# clock13.net
KiCad netlist of a schematic drawn in EAGLE
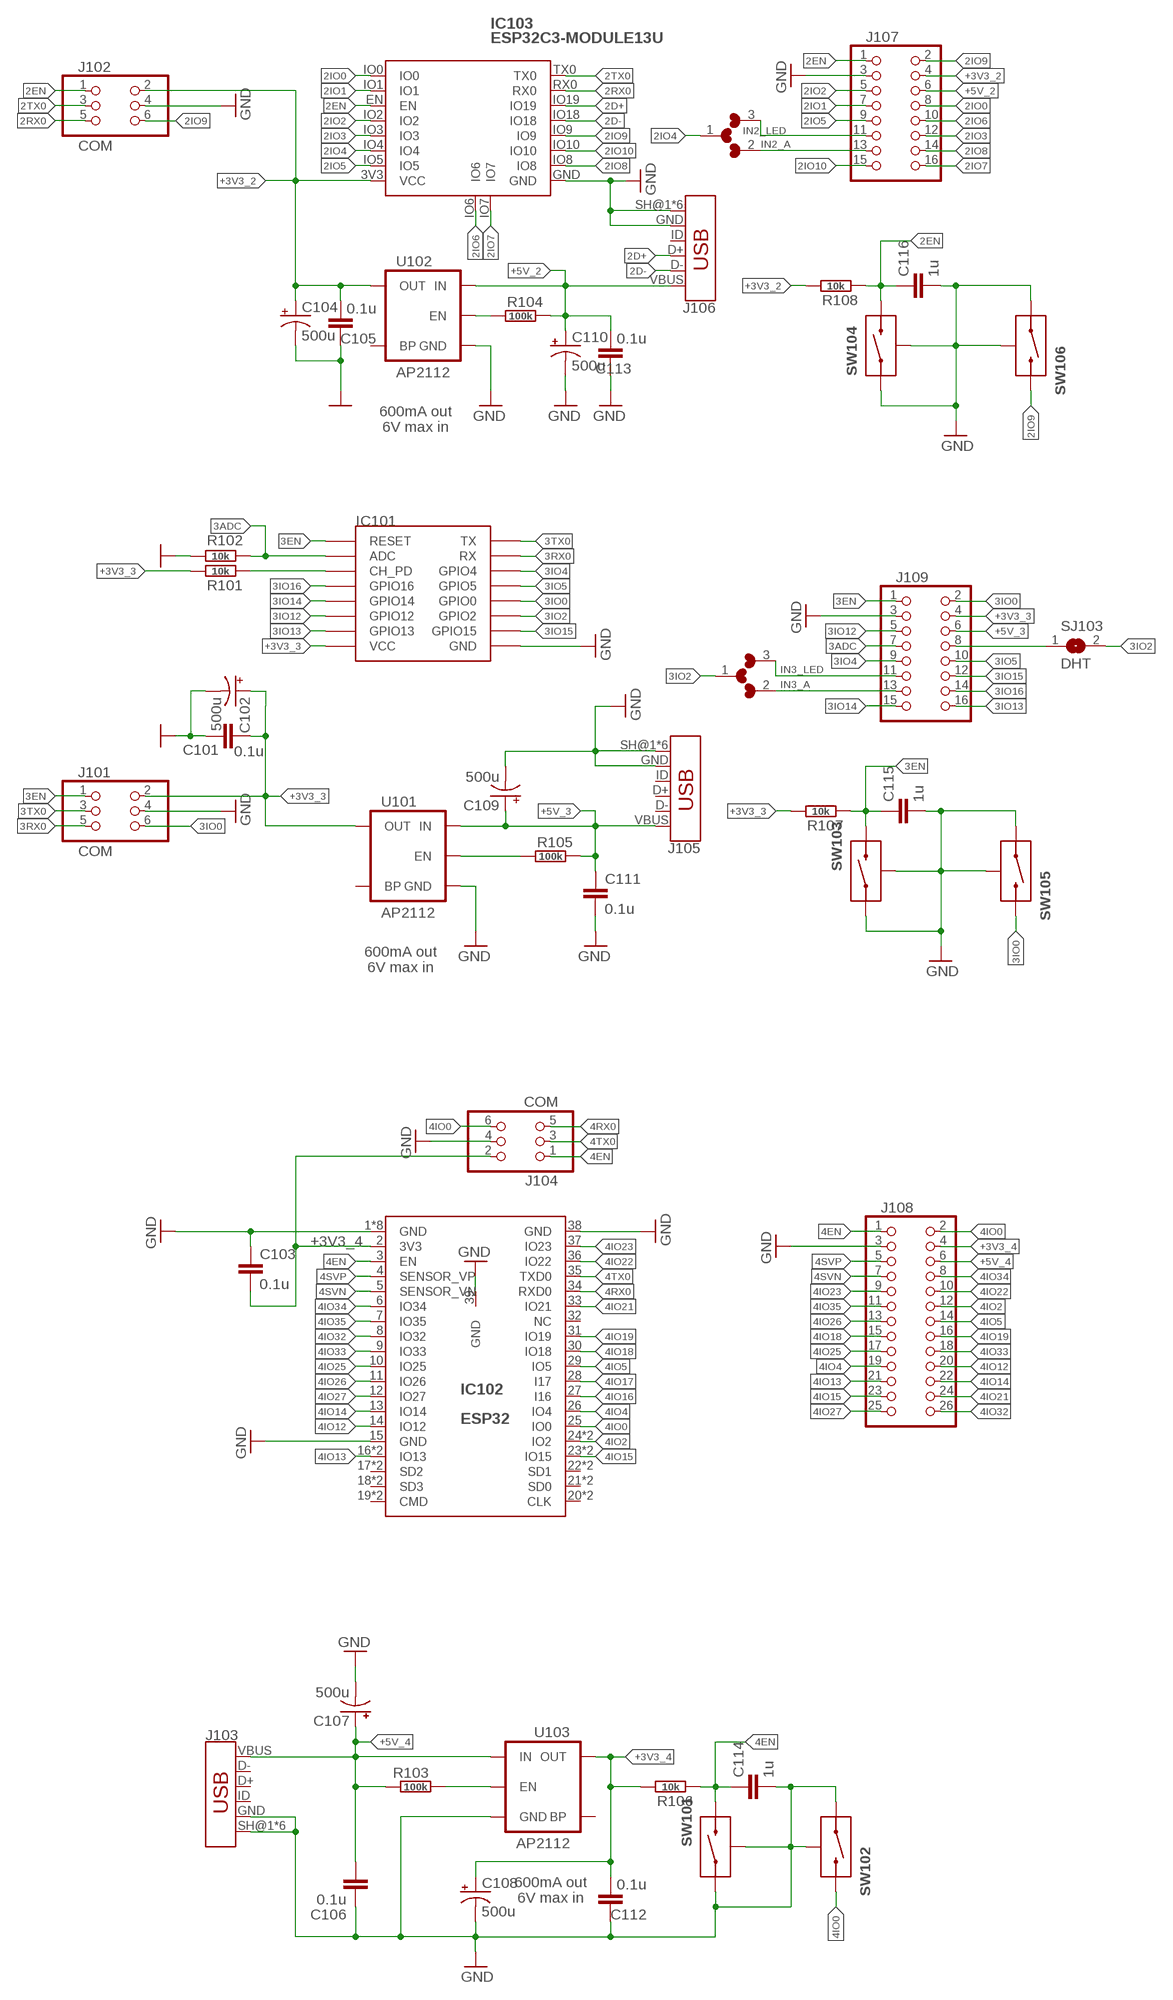
[diagram p0: schematic, sheet 1]

(export (version "E")
  (design (tool "Eeschema 10.0.6"))
  (components
    (comp (ref "C101")
      (value "0.1u")
      (footprint "eagle-import:0603-CAP")
      (libsource (lib "eagle-import") (part "CAP0603-CAP"))
    )
    (comp (ref "C102")
      (value "500u")
      (footprint "eagle-import:CPOL-RADIAL-100UF-25V")
      (libsource (lib "eagle-import") (part "CAP_POLPTH1"))
    )
    (comp (ref "C103")
      (value "0.1u")
      (footprint "eagle-import:0603-CAP")
      (libsource (lib "eagle-import") (part "CAP0603-CAP"))
    )
    (comp (ref "C104")
      (value "500u")
      (footprint "eagle-import:CPOL-RADIAL-100UF-25V")
      (libsource (lib "eagle-import") (part "CAP_POLPTH1"))
    )
    (comp (ref "C105")
      (value "0.1u")
      (footprint "eagle-import:0603-CAP")
      (libsource (lib "eagle-import") (part "CAP0603-CAP"))
    )
    (comp (ref "C106")
      (value "0.1u")
      (footprint "eagle-import:0603-CAP")
      (libsource (lib "eagle-import") (part "CAP0603-CAP"))
    )
    (comp (ref "C107")
      (value "500u")
      (footprint "eagle-import:CPOL-RADIAL-100UF-25V")
      (libsource (lib "eagle-import") (part "CAP_POLPTH1"))
    )
    (comp (ref "C108")
      (value "500u")
      (footprint "eagle-import:CPOL-RADIAL-100UF-25V")
      (libsource (lib "eagle-import") (part "CAP_POLPTH1"))
    )
    (comp (ref "C109")
      (value "500u")
      (footprint "eagle-import:CPOL-RADIAL-100UF-25V")
      (libsource (lib "eagle-import") (part "CAP_POLPTH1"))
    )
    (comp (ref "C110")
      (value "500u")
      (footprint "eagle-import:CPOL-RADIAL-100UF-25V")
      (libsource (lib "eagle-import") (part "CAP_POLPTH1"))
    )
    (comp (ref "C111")
      (value "0.1u")
      (footprint "eagle-import:0603-CAP")
      (libsource (lib "eagle-import") (part "CAP0603-CAP"))
    )
    (comp (ref "C112")
      (value "0.1u")
      (footprint "eagle-import:0603-CAP")
      (libsource (lib "eagle-import") (part "CAP0603-CAP"))
    )
    (comp (ref "C113")
      (value "0.1u")
      (footprint "eagle-import:0603-CAP")
      (libsource (lib "eagle-import") (part "CAP0603-CAP"))
    )
    (comp (ref "C114")
      (value "1u")
      (footprint "eagle-import:0603-CAP")
      (libsource (lib "eagle-import") (part "CAP0603-CAP"))
    )
    (comp (ref "C115")
      (value "1u")
      (footprint "eagle-import:0603-CAP")
      (libsource (lib "eagle-import") (part "CAP0603-CAP"))
    )
    (comp (ref "C116")
      (value "1u")
      (footprint "eagle-import:0603-CAP")
      (libsource (lib "eagle-import") (part "CAP0603-CAP"))
    )
    (comp (ref "IC101")
      (value "ESP12SMD")
      (footprint "eagle-import:ESP12-SMD")
      (libsource (lib "eagle-import") (part "ESP12SMD"))
    )
    (comp (ref "IC102")
      (value "ESP32")
      (footprint "eagle-import:ESP32-WROOVER_WROOM")
      (libsource (lib "eagle-import") (part "ESP32-MODULEDUAL"))
    )
    (comp (ref "IC103")
      (value "ESP32C3-MODULE13U")
      (footprint "eagle-import:ESP32C3-13U")
      (libsource (lib "eagle-import") (part "ESP32C3-MODULE13U"))
    )
    (comp (ref "J101")
      (value "COM")
      (footprint "eagle-import:2X03_SMT")
      (libsource (lib "eagle-import") (part "HEADER-2X3SMT"))
    )
    (comp (ref "J102")
      (value "COM")
      (footprint "eagle-import:2X03_SMT")
      (libsource (lib "eagle-import") (part "HEADER-2X3SMT"))
    )
    (comp (ref "J103")
      (value "USB_MICRO-BFEMALE_SMT_")
      (footprint "eagle-import:USB-B-MICRO-SMD_MY")
      (libsource (lib "eagle-import") (part "USB_MICRO-BFEMALE_SMT_"))
    )
    (comp (ref "J104")
      (value "COM")
      (footprint "eagle-import:2X03_SMT")
      (libsource (lib "eagle-import") (part "HEADER-2X3SMT"))
    )
    (comp (ref "J105")
      (value "USB_MICRO-BFEMALE_SMT_")
      (footprint "eagle-import:USB-B-MICRO-SMD_MY")
      (libsource (lib "eagle-import") (part "USB_MICRO-BFEMALE_SMT_"))
    )
    (comp (ref "J106")
      (value "USB_MICRO-BFEMALE_SMT_")
      (footprint "eagle-import:USB-B-MICRO-SMD_MY")
      (libsource (lib "eagle-import") (part "USB_MICRO-BFEMALE_SMT_"))
    )
    (comp (ref "J107")
      (value "HEADER-2X8")
      (footprint "eagle-import:2X8")
      (libsource (lib "eagle-import") (part "HEADER-2X8"))
    )
    (comp (ref "J108")
      (value "HEADER-2X13")
      (footprint "eagle-import:2X13")
      (libsource (lib "eagle-import") (part "HEADER-2X13"))
    )
    (comp (ref "J109")
      (value "HEADER-2X8")
      (footprint "eagle-import:2X8")
      (libsource (lib "eagle-import") (part "HEADER-2X8"))
    )
    (comp (ref "R101")
      (value "10k")
      (footprint "eagle-import:R0603")
      (libsource (lib "eagle-import") (part "R-EU_R0603"))
    )
    (comp (ref "R102")
      (value "10k")
      (footprint "eagle-import:R0603")
      (libsource (lib "eagle-import") (part "R-EU_R0603"))
    )
    (comp (ref "R103")
      (value "100k")
      (footprint "eagle-import:R0603")
      (libsource (lib "eagle-import") (part "R-EU_R0603"))
    )
    (comp (ref "R104")
      (value "100k")
      (footprint "eagle-import:R0603")
      (libsource (lib "eagle-import") (part "R-EU_R0603"))
    )
    (comp (ref "R105")
      (value "100k")
      (footprint "eagle-import:R0603")
      (libsource (lib "eagle-import") (part "R-EU_R0603"))
    )
    (comp (ref "R106")
      (value "10k")
      (footprint "eagle-import:R0603")
      (libsource (lib "eagle-import") (part "R-EU_R0603"))
    )
    (comp (ref "R107")
      (value "10k")
      (footprint "eagle-import:R0603")
      (libsource (lib "eagle-import") (part "R-EU_R0603"))
    )
    (comp (ref "R108")
      (value "10k")
      (footprint "eagle-import:R0603")
      (libsource (lib "eagle-import") (part "R-EU_R0603"))
    )
    (comp (ref "SJ101")
      (value "L/W")
      (footprint "eagle-import:MICROBUILDER_SOLDERJUMPER_ARROW_NOPASTE_3")
      (libsource (lib "eagle-import") (part "MICROBUILDER_SOLDERJUMPER3"))
    )
    (comp (ref "SJ102")
      (value "L/W")
      (footprint "eagle-import:MICROBUILDER_SOLDERJUMPER_ARROW_NOPASTE_3")
      (libsource (lib "eagle-import") (part "MICROBUILDER_SOLDERJUMPER3"))
    )
    (comp (ref "SJ103")
      (value "DHT")
      (footprint "eagle-import:MICROBUILDER_SOLDERJUMPER_ARROW_NOPASTE")
      (libsource (lib "eagle-import") (part "MICROBUILDER_SOLDERJUMPER"))
    )
    (comp (ref "SW101")
      (value "RST")
      (footprint "eagle-import:MICROPUSH-BUT_TOP")
      (libsource (lib "eagle-import") (part "MICROSWITCH-BUTTON"))
    )
    (comp (ref "SW102")
      (value "PRG")
      (footprint "eagle-import:MICROPUSH-BUT_TOP")
      (libsource (lib "eagle-import") (part "MICROSWITCH-BUTTON"))
    )
    (comp (ref "SW103")
      (value "RST")
      (footprint "eagle-import:MICROPUSH-BUT_TOP")
      (libsource (lib "eagle-import") (part "MICROSWITCH-BUTTON"))
    )
    (comp (ref "SW104")
      (value "RST")
      (footprint "eagle-import:MICROPUSH-BUT_TOP")
      (libsource (lib "eagle-import") (part "MICROSWITCH-BUTTON"))
    )
    (comp (ref "SW105")
      (value "PRG")
      (footprint "eagle-import:MICROPUSH-BUT_TOP")
      (libsource (lib "eagle-import") (part "MICROSWITCH-BUTTON"))
    )
    (comp (ref "SW106")
      (value "PRG")
      (footprint "eagle-import:MICROPUSH-BUT_TOP")
      (libsource (lib "eagle-import") (part "MICROSWITCH-BUTTON"))
    )
    (comp (ref "U101")
      (value "AP2112")
      (footprint "eagle-import:SOT23-5")
      (libsource (lib "eagle-import") (part "V_REG_LDOSMD"))
    )
    (comp (ref "U102")
      (value "AP2112")
      (footprint "eagle-import:SOT23-5")
      (libsource (lib "eagle-import") (part "V_REG_LDOSMD"))
    )
    (comp (ref "U103")
      (value "AP2112")
      (footprint "eagle-import:SOT23-5")
      (libsource (lib "eagle-import") (part "V_REG_LDOSMD"))
    )
  )
  (nets
    (net (code "1") (name "+3V3_2") (class "Default")
      (node (ref "C104") (pin "1") (pinfunction "+_1") (pintype "passive"))
      (node (ref "C105") (pin "2") (pinfunction "2_2") (pintype "passive"))
      (node (ref "IC103") (pin "3V3") (pinfunction "VCC_3V3") (pintype "power_in"))
      (node (ref "J102") (pin "2") (pinfunction "2_2") (pintype "passive"))
      (node (ref "J107") (pin "4") (pinfunction "4_4") (pintype "passive"))
      (node (ref "R108") (pin "2") (pinfunction "2_2") (pintype "passive"))
      (node (ref "U102") (pin "5") (pinfunction "OUT_5") (pintype "passive"))
    )
    (net (code "2") (name "+3V3_3") (class "Default")
      (node (ref "C101") (pin "2") (pinfunction "2_2") (pintype "passive"))
      (node (ref "C102") (pin "1") (pinfunction "+_1") (pintype "passive"))
      (node (ref "IC101") (pin "VCC") (pinfunction "VCC_VCC") (pintype "bidirectional"))
      (node (ref "J101") (pin "2") (pinfunction "2_2") (pintype "passive"))
      (node (ref "J109") (pin "4") (pinfunction "4_4") (pintype "passive"))
      (node (ref "R101") (pin "2") (pinfunction "2_2") (pintype "passive"))
      (node (ref "R107") (pin "2") (pinfunction "2_2") (pintype "passive"))
      (node (ref "U101") (pin "5") (pinfunction "OUT_5") (pintype "passive"))
    )
    (net (code "3") (name "+3V3_4") (class "Default")
      (node (ref "C103") (pin "2") (pinfunction "2_2") (pintype "passive"))
      (node (ref "C108") (pin "1") (pinfunction "+_1") (pintype "passive"))
      (node (ref "C112") (pin "2") (pinfunction "2_2") (pintype "passive"))
      (node (ref "IC102") (pin "2") (pinfunction "3V3_2") (pintype "power_in"))
      (node (ref "J104") (pin "2") (pinfunction "2_2") (pintype "passive"))
      (node (ref "J108") (pin "4") (pinfunction "4_4") (pintype "passive"))
      (node (ref "R106") (pin "2") (pinfunction "2_2") (pintype "passive"))
      (node (ref "U103") (pin "5") (pinfunction "OUT_5") (pintype "passive"))
    )
    (net (code "4") (name "+5V_2") (class "Default")
      (node (ref "C110") (pin "1") (pinfunction "+_1") (pintype "passive"))
      (node (ref "C113") (pin "2") (pinfunction "2_2") (pintype "passive"))
      (node (ref "J106") (pin "VBUS") (pinfunction "VBUS_VBUS") (pintype "power_in"))
      (node (ref "J107") (pin "6") (pinfunction "6_6") (pintype "passive"))
      (node (ref "R104") (pin "1") (pinfunction "1_1") (pintype "passive"))
      (node (ref "U102") (pin "1") (pinfunction "IN_1") (pintype "input"))
    )
    (net (code "5") (name "+5V_3") (class "Default")
      (node (ref "C109") (pin "1") (pinfunction "+_1") (pintype "passive"))
      (node (ref "C111") (pin "1") (pinfunction "1_1") (pintype "passive"))
      (node (ref "J105") (pin "VBUS") (pinfunction "VBUS_VBUS") (pintype "power_in"))
      (node (ref "J109") (pin "6") (pinfunction "6_6") (pintype "passive"))
      (node (ref "R105") (pin "1") (pinfunction "1_1") (pintype "passive"))
      (node (ref "U101") (pin "1") (pinfunction "IN_1") (pintype "input"))
    )
    (net (code "6") (name "+5V_4") (class "Default")
      (node (ref "C106") (pin "1") (pinfunction "1_1") (pintype "passive"))
      (node (ref "C107") (pin "1") (pinfunction "+_1") (pintype "passive"))
      (node (ref "J103") (pin "VBUS") (pinfunction "VBUS_VBUS") (pintype "power_in"))
      (node (ref "J108") (pin "6") (pinfunction "6_6") (pintype "passive"))
      (node (ref "R103") (pin "1") (pinfunction "1_1") (pintype "passive"))
      (node (ref "U103") (pin "1") (pinfunction "IN_1") (pintype "input"))
    )
    (net (code "7") (name "/IN2_A") (class "Default")
      (node (ref "J107") (pin "13") (pinfunction "13_13") (pintype "passive"))
      (node (ref "SJ101") (pin "2") (pinfunction "2_2") (pintype "passive"))
    )
    (net (code "8") (name "/IN2_LED") (class "Default")
      (node (ref "J107") (pin "11") (pinfunction "11_11") (pintype "passive"))
      (node (ref "SJ101") (pin "3") (pinfunction "3_3") (pintype "passive"))
    )
    (net (code "9") (name "/IN3_A") (class "Default")
      (node (ref "J109") (pin "13") (pinfunction "13_13") (pintype "passive"))
      (node (ref "SJ102") (pin "2") (pinfunction "2_2") (pintype "passive"))
    )
    (net (code "10") (name "/IN3_LED") (class "Default")
      (node (ref "J109") (pin "11") (pinfunction "11_11") (pintype "passive"))
      (node (ref "SJ102") (pin "3") (pinfunction "3_3") (pintype "passive"))
    )
    (net (code "11") (name "2D+") (class "Default")
      (node (ref "IC103") (pin "IO19") (pinfunction "IO19_IO19") (pintype "bidirectional"))
      (node (ref "J106") (pin "D+") (pinfunction "D+_D+") (pintype "bidirectional"))
    )
    (net (code "12") (name "2D-") (class "Default")
      (node (ref "IC103") (pin "IO18") (pinfunction "IO18_IO18") (pintype "bidirectional"))
      (node (ref "J106") (pin "D-") (pinfunction "D-_D-") (pintype "bidirectional"))
    )
    (net (code "13") (name "2EN") (class "Default")
      (node (ref "C116") (pin "1") (pinfunction "1_1") (pintype "passive"))
      (node (ref "IC103") (pin "EN") (pinfunction "EN_EN") (pintype "bidirectional"))
      (node (ref "J102") (pin "1") (pinfunction "1_1") (pintype "passive"))
      (node (ref "J107") (pin "1") (pinfunction "1_1") (pintype "passive"))
      (node (ref "R108") (pin "1") (pinfunction "1_1") (pintype "passive"))
      (node (ref "SW104") (pin "B") (pinfunction "B_B") (pintype "passive"))
    )
    (net (code "14") (name "2IO0") (class "Default")
      (node (ref "IC103") (pin "IO0") (pinfunction "IO0_IO0") (pintype "bidirectional"))
      (node (ref "J107") (pin "8") (pinfunction "8_8") (pintype "passive"))
    )
    (net (code "15") (name "2IO1") (class "Default")
      (node (ref "IC103") (pin "IO1") (pinfunction "IO1_IO1") (pintype "bidirectional"))
      (node (ref "J107") (pin "7") (pinfunction "7_7") (pintype "passive"))
    )
    (net (code "16") (name "2IO2") (class "Default")
      (node (ref "IC103") (pin "IO2") (pinfunction "IO2_IO2") (pintype "bidirectional"))
      (node (ref "J107") (pin "5") (pinfunction "5_5") (pintype "passive"))
    )
    (net (code "17") (name "2IO3") (class "Default")
      (node (ref "IC103") (pin "IO3") (pinfunction "IO3_IO3") (pintype "bidirectional"))
      (node (ref "J107") (pin "12") (pinfunction "12_12") (pintype "passive"))
    )
    (net (code "18") (name "2IO4") (class "Default")
      (node (ref "IC103") (pin "IO4") (pinfunction "IO4_IO4") (pintype "bidirectional"))
      (node (ref "SJ101") (pin "1") (pinfunction "1_1") (pintype "passive"))
    )
    (net (code "19") (name "2IO5") (class "Default")
      (node (ref "IC103") (pin "IO5") (pinfunction "IO5_IO5") (pintype "bidirectional"))
      (node (ref "J107") (pin "9") (pinfunction "9_9") (pintype "passive"))
    )
    (net (code "20") (name "2IO6") (class "Default")
      (node (ref "IC103") (pin "IO6") (pinfunction "IO6_IO6") (pintype "bidirectional"))
      (node (ref "J107") (pin "10") (pinfunction "10_10") (pintype "passive"))
    )
    (net (code "21") (name "2IO7") (class "Default")
      (node (ref "IC103") (pin "IO7") (pinfunction "IO7_IO7") (pintype "bidirectional"))
      (node (ref "J107") (pin "16") (pinfunction "16_16") (pintype "passive"))
    )
    (net (code "22") (name "2IO8") (class "Default")
      (node (ref "IC103") (pin "IO8") (pinfunction "IO8_IO8") (pintype "bidirectional"))
      (node (ref "J107") (pin "14") (pinfunction "14_14") (pintype "passive"))
    )
    (net (code "23") (name "2IO9") (class "Default")
      (node (ref "IC103") (pin "IO9") (pinfunction "IO9_IO9") (pintype "bidirectional"))
      (node (ref "J102") (pin "6") (pinfunction "6_6") (pintype "passive"))
      (node (ref "J107") (pin "2") (pinfunction "2_2") (pintype "passive"))
      (node (ref "SW106") (pin "B") (pinfunction "B_B") (pintype "passive"))
    )
    (net (code "24") (name "2IO10") (class "Default")
      (node (ref "IC103") (pin "IO10") (pinfunction "IO10_IO10") (pintype "bidirectional"))
      (node (ref "J107") (pin "15") (pinfunction "15_15") (pintype "passive"))
    )
    (net (code "25") (name "2RX0") (class "Default")
      (node (ref "IC103") (pin "RX0") (pinfunction "RX0_RX0") (pintype "input"))
      (node (ref "J102") (pin "5") (pinfunction "5_5") (pintype "passive"))
    )
    (net (code "26") (name "2TX0") (class "Default")
      (node (ref "IC103") (pin "TX0") (pinfunction "TX0_TX0") (pintype "output"))
      (node (ref "J102") (pin "3") (pinfunction "3_3") (pintype "passive"))
    )
    (net (code "27") (name "3ADC") (class "Default")
      (node (ref "IC101") (pin "ADC") (pinfunction "ADC_ADC") (pintype "bidirectional"))
      (node (ref "J109") (pin "7") (pinfunction "7_7") (pintype "passive"))
      (node (ref "R102") (pin "1") (pinfunction "1_1") (pintype "passive"))
    )
    (net (code "28") (name "3EN") (class "Default")
      (node (ref "C115") (pin "1") (pinfunction "1_1") (pintype "passive"))
      (node (ref "IC101") (pin "RESET") (pinfunction "RESET_RESET") (pintype "bidirectional"))
      (node (ref "J101") (pin "1") (pinfunction "1_1") (pintype "passive"))
      (node (ref "J109") (pin "1") (pinfunction "1_1") (pintype "passive"))
      (node (ref "R107") (pin "1") (pinfunction "1_1") (pintype "passive"))
      (node (ref "SW103") (pin "B") (pinfunction "B_B") (pintype "passive"))
    )
    (net (code "29") (name "3IO0") (class "Default")
      (node (ref "IC101") (pin "GPIO0") (pinfunction "GPIO0_GPIO0") (pintype "bidirectional"))
      (node (ref "J101") (pin "6") (pinfunction "6_6") (pintype "passive"))
      (node (ref "J109") (pin "2") (pinfunction "2_2") (pintype "passive"))
      (node (ref "SW105") (pin "B") (pinfunction "B_B") (pintype "passive"))
    )
    (net (code "30") (name "3IO2") (class "Default")
      (node (ref "IC101") (pin "GPIO2") (pinfunction "GPIO2_GPIO2") (pintype "bidirectional"))
      (node (ref "SJ102") (pin "1") (pinfunction "1_1") (pintype "passive"))
      (node (ref "SJ103") (pin "2") (pinfunction "2_2") (pintype "passive"))
    )
    (net (code "31") (name "3IO4") (class "Default")
      (node (ref "IC101") (pin "GPIO4") (pinfunction "GPIO4_GPIO4") (pintype "bidirectional"))
      (node (ref "J109") (pin "9") (pinfunction "9_9") (pintype "passive"))
    )
    (net (code "32") (name "3IO5") (class "Default")
      (node (ref "IC101") (pin "GPIO5") (pinfunction "GPIO5_GPIO5") (pintype "bidirectional"))
      (node (ref "J109") (pin "10") (pinfunction "10_10") (pintype "passive"))
    )
    (net (code "33") (name "3IO12") (class "Default")
      (node (ref "IC101") (pin "GPIO12") (pinfunction "GPIO12_GPIO12") (pintype "bidirectional"))
      (node (ref "J109") (pin "5") (pinfunction "5_5") (pintype "passive"))
    )
    (net (code "34") (name "3IO13") (class "Default")
      (node (ref "IC101") (pin "GPIO13") (pinfunction "GPIO13_GPIO13") (pintype "bidirectional"))
      (node (ref "J109") (pin "16") (pinfunction "16_16") (pintype "passive"))
    )
    (net (code "35") (name "3IO14") (class "Default")
      (node (ref "IC101") (pin "GPIO14") (pinfunction "GPIO14_GPIO14") (pintype "bidirectional"))
      (node (ref "J109") (pin "15") (pinfunction "15_15") (pintype "passive"))
    )
    (net (code "36") (name "3IO15") (class "Default")
      (node (ref "IC101") (pin "GPIO15") (pinfunction "GPIO15_GPIO15") (pintype "bidirectional"))
      (node (ref "J109") (pin "12") (pinfunction "12_12") (pintype "passive"))
    )
    (net (code "37") (name "3IO16") (class "Default")
      (node (ref "IC101") (pin "GPIO16") (pinfunction "GPIO16_GPIO16") (pintype "bidirectional"))
      (node (ref "J109") (pin "14") (pinfunction "14_14") (pintype "passive"))
    )
    (net (code "38") (name "3RX0") (class "Default")
      (node (ref "IC101") (pin "RXD0") (pinfunction "RX_RXD0") (pintype "bidirectional"))
      (node (ref "J101") (pin "5") (pinfunction "5_5") (pintype "passive"))
    )
    (net (code "39") (name "3TX0") (class "Default")
      (node (ref "IC101") (pin "TXD0") (pinfunction "TX_TXD0") (pintype "bidirectional"))
      (node (ref "J101") (pin "3") (pinfunction "3_3") (pintype "passive"))
    )
    (net (code "40") (name "4EN") (class "Default")
      (node (ref "C114") (pin "1") (pinfunction "1_1") (pintype "passive"))
      (node (ref "IC102") (pin "3") (pinfunction "EN_3") (pintype "input"))
      (node (ref "J104") (pin "1") (pinfunction "1_1") (pintype "passive"))
      (node (ref "J108") (pin "1") (pinfunction "1_1") (pintype "passive"))
      (node (ref "R106") (pin "1") (pinfunction "1_1") (pintype "passive"))
      (node (ref "SW101") (pin "B") (pinfunction "B_B") (pintype "passive"))
    )
    (net (code "41") (name "4IO0") (class "Default")
      (node (ref "IC102") (pin "25") (pinfunction "IO0_25") (pintype "bidirectional"))
      (node (ref "J104") (pin "6") (pinfunction "6_6") (pintype "passive"))
      (node (ref "J108") (pin "2") (pinfunction "2_2") (pintype "passive"))
      (node (ref "SW102") (pin "B") (pinfunction "B_B") (pintype "passive"))
    )
    (net (code "42") (name "4IO2") (class "Default")
      (node (ref "IC102") (pin "24") (pinfunction "IO2_24") (pintype "bidirectional"))
      (node (ref "IC102") (pin "48") (pinfunction "IO2_48") (pintype "bidirectional"))
      (node (ref "J108") (pin "12") (pinfunction "12_12") (pintype "passive"))
    )
    (net (code "43") (name "4IO4") (class "Default")
      (node (ref "IC102") (pin "26") (pinfunction "IO4_26") (pintype "bidirectional"))
      (node (ref "J108") (pin "19") (pinfunction "19_19") (pintype "passive"))
    )
    (net (code "44") (name "4IO5") (class "Default")
      (node (ref "IC102") (pin "29") (pinfunction "IO5_29") (pintype "bidirectional"))
      (node (ref "J108") (pin "14") (pinfunction "14_14") (pintype "passive"))
    )
    (net (code "45") (name "4IO12") (class "Default")
      (node (ref "IC102") (pin "14") (pinfunction "IO12_14") (pintype "bidirectional"))
      (node (ref "J108") (pin "20") (pinfunction "20_20") (pintype "passive"))
    )
    (net (code "46") (name "4IO13") (class "Default")
      (node (ref "IC102") (pin "16") (pinfunction "IO13_16") (pintype "bidirectional"))
      (node (ref "IC102") (pin "40") (pinfunction "IO13_40") (pintype "bidirectional"))
      (node (ref "J108") (pin "21") (pinfunction "21_21") (pintype "passive"))
    )
    (net (code "47") (name "4IO14") (class "Default")
      (node (ref "IC102") (pin "13") (pinfunction "IO14_13") (pintype "bidirectional"))
      (node (ref "J108") (pin "22") (pinfunction "22_22") (pintype "passive"))
    )
    (net (code "48") (name "4IO15") (class "Default")
      (node (ref "IC102") (pin "23") (pinfunction "IO15_23") (pintype "bidirectional"))
      (node (ref "IC102") (pin "47") (pinfunction "IO15_47") (pintype "bidirectional"))
      (node (ref "J108") (pin "23") (pinfunction "23_23") (pintype "passive"))
    )
    (net (code "49") (name "4IO16") (class "Default")
      (node (ref "IC102") (pin "27") (pinfunction "I16_27") (pintype "bidirectional"))
    )
    (net (code "50") (name "4IO17") (class "Default")
      (node (ref "IC102") (pin "28") (pinfunction "I17_28") (pintype "bidirectional"))
    )
    (net (code "51") (name "4IO18") (class "Default")
      (node (ref "IC102") (pin "30") (pinfunction "IO18_30") (pintype "bidirectional"))
      (node (ref "J108") (pin "15") (pinfunction "15_15") (pintype "passive"))
    )
    (net (code "52") (name "4IO19") (class "Default")
      (node (ref "IC102") (pin "31") (pinfunction "IO19_31") (pintype "bidirectional"))
      (node (ref "J108") (pin "16") (pinfunction "16_16") (pintype "passive"))
    )
    (net (code "53") (name "4IO21") (class "Default")
      (node (ref "IC102") (pin "33") (pinfunction "IO21_33") (pintype "bidirectional"))
      (node (ref "J108") (pin "24") (pinfunction "24_24") (pintype "passive"))
    )
    (net (code "54") (name "4IO22") (class "Default")
      (node (ref "IC102") (pin "36") (pinfunction "IO22_36") (pintype "bidirectional"))
      (node (ref "J108") (pin "10") (pinfunction "10_10") (pintype "passive"))
    )
    (net (code "55") (name "4IO23") (class "Default")
      (node (ref "IC102") (pin "37") (pinfunction "IO23_37") (pintype "bidirectional"))
      (node (ref "J108") (pin "9") (pinfunction "9_9") (pintype "passive"))
    )
    (net (code "56") (name "4IO25") (class "Default")
      (node (ref "IC102") (pin "10") (pinfunction "IO25_10") (pintype "bidirectional"))
      (node (ref "J108") (pin "17") (pinfunction "17_17") (pintype "passive"))
    )
    (net (code "57") (name "4IO26") (class "Default")
      (node (ref "IC102") (pin "11") (pinfunction "IO26_11") (pintype "bidirectional"))
      (node (ref "J108") (pin "13") (pinfunction "13_13") (pintype "passive"))
    )
    (net (code "58") (name "4IO27") (class "Default")
      (node (ref "IC102") (pin "12") (pinfunction "IO27_12") (pintype "bidirectional"))
      (node (ref "J108") (pin "25") (pinfunction "25_25") (pintype "passive"))
    )
    (net (code "59") (name "4IO32") (class "Default")
      (node (ref "IC102") (pin "8") (pinfunction "IO32_8") (pintype "bidirectional"))
      (node (ref "J108") (pin "26") (pinfunction "26_26") (pintype "passive"))
    )
    (net (code "60") (name "4IO33") (class "Default")
      (node (ref "IC102") (pin "9") (pinfunction "IO33_9") (pintype "bidirectional"))
      (node (ref "J108") (pin "18") (pinfunction "18_18") (pintype "passive"))
    )
    (net (code "61") (name "4IO34") (class "Default")
      (node (ref "IC102") (pin "6") (pinfunction "IO34_6") (pintype "bidirectional"))
      (node (ref "J108") (pin "8") (pinfunction "8_8") (pintype "passive"))
    )
    (net (code "62") (name "4IO35") (class "Default")
      (node (ref "IC102") (pin "7") (pinfunction "IO35_7") (pintype "bidirectional"))
      (node (ref "J108") (pin "11") (pinfunction "11_11") (pintype "passive"))
    )
    (net (code "63") (name "4RX0") (class "Default")
      (node (ref "IC102") (pin "34") (pinfunction "RXD0_34") (pintype "input"))
      (node (ref "J104") (pin "5") (pinfunction "5_5") (pintype "passive"))
    )
    (net (code "64") (name "4SVN") (class "Default")
      (node (ref "IC102") (pin "5") (pinfunction "SENSOR_VN_5") (pintype "input"))
      (node (ref "J108") (pin "7") (pinfunction "7_7") (pintype "passive"))
    )
    (net (code "65") (name "4SVP") (class "Default")
      (node (ref "IC102") (pin "4") (pinfunction "SENSOR_VP_4") (pintype "input"))
      (node (ref "J108") (pin "5") (pinfunction "5_5") (pintype "passive"))
    )
    (net (code "66") (name "4TX0") (class "Default")
      (node (ref "IC102") (pin "35") (pinfunction "TXD0_35") (pintype "output"))
      (node (ref "J104") (pin "3") (pinfunction "3_3") (pintype "passive"))
    )
    (net (code "67") (name "GND") (class "Default")
      (node (ref "C101") (pin "1") (pinfunction "1_1") (pintype "passive"))
      (node (ref "C102") (pin "2") (pinfunction "-_2") (pintype "passive"))
      (node (ref "C103") (pin "1") (pinfunction "1_1") (pintype "passive"))
      (node (ref "C104") (pin "2") (pinfunction "-_2") (pintype "passive"))
      (node (ref "C105") (pin "1") (pinfunction "1_1") (pintype "passive"))
      (node (ref "C106") (pin "2") (pinfunction "2_2") (pintype "passive"))
      (node (ref "C107") (pin "2") (pinfunction "-_2") (pintype "passive"))
      (node (ref "C108") (pin "2") (pinfunction "-_2") (pintype "passive"))
      (node (ref "C109") (pin "2") (pinfunction "-_2") (pintype "passive"))
      (node (ref "C110") (pin "2") (pinfunction "-_2") (pintype "passive"))
      (node (ref "C111") (pin "2") (pinfunction "2_2") (pintype "passive"))
      (node (ref "C112") (pin "1") (pinfunction "1_1") (pintype "passive"))
      (node (ref "C113") (pin "1") (pinfunction "1_1") (pintype "passive"))
      (node (ref "C114") (pin "2") (pinfunction "2_2") (pintype "passive"))
      (node (ref "C115") (pin "2") (pinfunction "2_2") (pintype "passive"))
      (node (ref "C116") (pin "2") (pinfunction "2_2") (pintype "passive"))
      (node (ref "IC101") (pin "GND") (pinfunction "GND_GND") (pintype "bidirectional"))
      (node (ref "IC102") (pin "1") (pinfunction "GND_1") (pintype "power_in"))
      (node (ref "IC102") (pin "15") (pinfunction "GND_15") (pintype "power_in"))
      (node (ref "IC102") (pin "38") (pinfunction "GND_38") (pintype "power_in"))
      (node (ref "IC102") (pin "39") (pinfunction "GND_39") (pintype "power_in"))
      (node (ref "IC102") (pin "GND") (pinfunction "GND_GND") (pintype "power_in"))
      (node (ref "IC102") (pin "PAD$1") (pinfunction "GND_PAD$1") (pintype "power_in"))
      (node (ref "IC102") (pin "PAD$4") (pinfunction "GND_PAD$4") (pintype "power_in"))
      (node (ref "IC102") (pin "PAD$5") (pinfunction "GND_PAD$5") (pintype "power_in"))
      (node (ref "IC102") (pin "PAD$7") (pinfunction "GND_PAD$7") (pintype "power_in"))
      (node (ref "IC102") (pin "PAD$8") (pinfunction "GND_PAD$8") (pintype "power_in"))
      (node (ref "IC102") (pin "PAD$9") (pinfunction "GND_PAD$9") (pintype "power_in"))
      (node (ref "IC103") (pin "GND") (pinfunction "GND_GND") (pintype "power_in"))
      (node (ref "J101") (pin "4") (pinfunction "4_4") (pintype "passive"))
      (node (ref "J102") (pin "4") (pinfunction "4_4") (pintype "passive"))
      (node (ref "J103") (pin "GND") (pinfunction "GND_GND") (pintype "power_in"))
      (node (ref "J103") (pin "SH@1") (pinfunction "SHIELD_SH@1") (pintype "bidirectional"))
      (node (ref "J103") (pin "SH@2") (pinfunction "SHIELD_SH@2") (pintype "bidirectional"))
      (node (ref "J103") (pin "SH@3") (pinfunction "SHIELD_SH@3") (pintype "bidirectional"))
      (node (ref "J103") (pin "SH@4") (pinfunction "SHIELD_SH@4") (pintype "bidirectional"))
      (node (ref "J103") (pin "SH@5") (pinfunction "SHIELD_SH@5") (pintype "bidirectional"))
      (node (ref "J103") (pin "SH@6") (pinfunction "SHIELD_SH@6") (pintype "bidirectional"))
      (node (ref "J104") (pin "4") (pinfunction "4_4") (pintype "passive"))
      (node (ref "J105") (pin "GND") (pinfunction "GND_GND") (pintype "power_in"))
      (node (ref "J105") (pin "SH@1") (pinfunction "SHIELD_SH@1") (pintype "bidirectional"))
      (node (ref "J105") (pin "SH@2") (pinfunction "SHIELD_SH@2") (pintype "bidirectional"))
      (node (ref "J105") (pin "SH@3") (pinfunction "SHIELD_SH@3") (pintype "bidirectional"))
      (node (ref "J105") (pin "SH@4") (pinfunction "SHIELD_SH@4") (pintype "bidirectional"))
      (node (ref "J105") (pin "SH@5") (pinfunction "SHIELD_SH@5") (pintype "bidirectional"))
      (node (ref "J105") (pin "SH@6") (pinfunction "SHIELD_SH@6") (pintype "bidirectional"))
      (node (ref "J106") (pin "GND") (pinfunction "GND_GND") (pintype "power_in"))
      (node (ref "J106") (pin "SH@1") (pinfunction "SHIELD_SH@1") (pintype "bidirectional"))
      (node (ref "J106") (pin "SH@2") (pinfunction "SHIELD_SH@2") (pintype "bidirectional"))
      (node (ref "J106") (pin "SH@3") (pinfunction "SHIELD_SH@3") (pintype "bidirectional"))
      (node (ref "J106") (pin "SH@4") (pinfunction "SHIELD_SH@4") (pintype "bidirectional"))
      (node (ref "J106") (pin "SH@5") (pinfunction "SHIELD_SH@5") (pintype "bidirectional"))
      (node (ref "J106") (pin "SH@6") (pinfunction "SHIELD_SH@6") (pintype "bidirectional"))
      (node (ref "J107") (pin "3") (pinfunction "3_3") (pintype "passive"))
      (node (ref "J108") (pin "3") (pinfunction "3_3") (pintype "passive"))
      (node (ref "J109") (pin "3") (pinfunction "3_3") (pintype "passive"))
      (node (ref "R102") (pin "2") (pinfunction "2_2") (pintype "passive"))
      (node (ref "SW101") (pin "A") (pinfunction "A_A") (pintype "passive"))
      (node (ref "SW101") (pin "SH0") (pinfunction "SH_SH0") (pintype "power_in"))
      (node (ref "SW102") (pin "A") (pinfunction "A_A") (pintype "passive"))
      (node (ref "SW102") (pin "SH0") (pinfunction "SH_SH0") (pintype "power_in"))
      (node (ref "SW103") (pin "A") (pinfunction "A_A") (pintype "passive"))
      (node (ref "SW103") (pin "SH0") (pinfunction "SH_SH0") (pintype "power_in"))
      (node (ref "SW104") (pin "A") (pinfunction "A_A") (pintype "passive"))
      (node (ref "SW104") (pin "SH0") (pinfunction "SH_SH0") (pintype "power_in"))
      (node (ref "SW105") (pin "A") (pinfunction "A_A") (pintype "passive"))
      (node (ref "SW105") (pin "SH0") (pinfunction "SH_SH0") (pintype "power_in"))
      (node (ref "SW106") (pin "A") (pinfunction "A_A") (pintype "passive"))
      (node (ref "SW106") (pin "SH0") (pinfunction "SH_SH0") (pintype "power_in"))
      (node (ref "U101") (pin "2") (pinfunction "GND_2") (pintype "input"))
      (node (ref "U102") (pin "2") (pinfunction "GND_2") (pintype "input"))
      (node (ref "U103") (pin "2") (pinfunction "GND_2") (pintype "input"))
    )
    (net (code "68") (name "Net-(IC101-PadCH_PD)") (class "Default")
      (node (ref "IC101") (pin "CH_PD") (pinfunction "CH_PD_CH_PD") (pintype "bidirectional"))
      (node (ref "R101") (pin "1") (pinfunction "1_1") (pintype "passive"))
    )
    (net (code "69") (name "Net-(J109-Pad8)") (class "Default")
      (node (ref "J109") (pin "8") (pinfunction "8_8") (pintype "passive"))
      (node (ref "SJ103") (pin "1") (pinfunction "1_1") (pintype "passive"))
    )
    (net (code "70") (name "Net-(U101-EN)") (class "Default")
      (node (ref "R105") (pin "2") (pinfunction "2_2") (pintype "passive"))
      (node (ref "U101") (pin "3") (pinfunction "EN_3") (pintype "input"))
    )
    (net (code "71") (name "Net-(U102-EN)") (class "Default")
      (node (ref "R104") (pin "2") (pinfunction "2_2") (pintype "passive"))
      (node (ref "U102") (pin "3") (pinfunction "EN_3") (pintype "input"))
    )
    (net (code "72") (name "Net-(U103-EN)") (class "Default")
      (node (ref "R103") (pin "2") (pinfunction "2_2") (pintype "passive"))
      (node (ref "U103") (pin "3") (pinfunction "EN_3") (pintype "input"))
    )
    (net (code "73") (name "unconnected-(IC102-CLK-Pad20)") (class "Default")
      (node (ref "IC102") (pin "20") (pinfunction "CLK_20") (pintype "no_connect"))
    )
    (net (code "74") (name "unconnected-(IC102-CLK-Pad44)") (class "Default")
      (node (ref "IC102") (pin "44") (pinfunction "CLK_44") (pintype "no_connect"))
    )
    (net (code "75") (name "unconnected-(IC102-CMD-Pad19)") (class "Default")
      (node (ref "IC102") (pin "19") (pinfunction "CMD_19") (pintype "no_connect"))
    )
    (net (code "76") (name "unconnected-(IC102-CMD-Pad43)") (class "Default")
      (node (ref "IC102") (pin "43") (pinfunction "CMD_43") (pintype "no_connect"))
    )
    (net (code "77") (name "unconnected-(IC102-NC-Pad32)") (class "Default")
      (node (ref "IC102") (pin "32") (pinfunction "NC_32") (pintype "no_connect"))
    )
    (net (code "78") (name "unconnected-(IC102-SD0-Pad21)") (class "Default")
      (node (ref "IC102") (pin "21") (pinfunction "SD0_21") (pintype "no_connect"))
    )
    (net (code "79") (name "unconnected-(IC102-SD0-Pad45)") (class "Default")
      (node (ref "IC102") (pin "45") (pinfunction "SD0_45") (pintype "no_connect"))
    )
    (net (code "80") (name "unconnected-(IC102-SD1-Pad22)") (class "Default")
      (node (ref "IC102") (pin "22") (pinfunction "SD1_22") (pintype "no_connect"))
    )
    (net (code "81") (name "unconnected-(IC102-SD1-Pad46)") (class "Default")
      (node (ref "IC102") (pin "46") (pinfunction "SD1_46") (pintype "no_connect"))
    )
    (net (code "82") (name "unconnected-(IC102-SD2-Pad17)") (class "Default")
      (node (ref "IC102") (pin "17") (pinfunction "SD2_17") (pintype "no_connect"))
    )
    (net (code "83") (name "unconnected-(IC102-SD2-Pad41)") (class "Default")
      (node (ref "IC102") (pin "41") (pinfunction "SD2_41") (pintype "no_connect"))
    )
    (net (code "84") (name "unconnected-(IC102-SD3-Pad18)") (class "Default")
      (node (ref "IC102") (pin "18") (pinfunction "SD3_18") (pintype "no_connect"))
    )
    (net (code "85") (name "unconnected-(IC102-SD3-Pad42)") (class "Default")
      (node (ref "IC102") (pin "42") (pinfunction "SD3_42") (pintype "no_connect"))
    )
    (net (code "86") (name "unconnected-(J103-PadD+)") (class "Default")
      (node (ref "J103") (pin "D+") (pinfunction "D+_D+") (pintype "bidirectional"))
    )
    (net (code "87") (name "unconnected-(J103-PadD-)") (class "Default")
      (node (ref "J103") (pin "D-") (pinfunction "D-_D-") (pintype "bidirectional"))
    )
    (net (code "88") (name "unconnected-(J103-PadID)") (class "Default")
      (node (ref "J103") (pin "ID") (pinfunction "ID_ID") (pintype "bidirectional"))
    )
    (net (code "89") (name "unconnected-(J105-PadD+)") (class "Default")
      (node (ref "J105") (pin "D+") (pinfunction "D+_D+") (pintype "bidirectional"))
    )
    (net (code "90") (name "unconnected-(J105-PadD-)") (class "Default")
      (node (ref "J105") (pin "D-") (pinfunction "D-_D-") (pintype "bidirectional"))
    )
    (net (code "91") (name "unconnected-(J105-PadID)") (class "Default")
      (node (ref "J105") (pin "ID") (pinfunction "ID_ID") (pintype "bidirectional"))
    )
    (net (code "92") (name "unconnected-(J106-PadID)") (class "Default")
      (node (ref "J106") (pin "ID") (pinfunction "ID_ID") (pintype "bidirectional"))
    )
    (net (code "93") (name "unconnected-(U101-BP-Pad4)") (class "Default")
      (node (ref "U101") (pin "4") (pinfunction "BP_4") (pintype "input"))
    )
    (net (code "94") (name "unconnected-(U102-BP-Pad4)") (class "Default")
      (node (ref "U102") (pin "4") (pinfunction "BP_4") (pintype "input"))
    )
    (net (code "95") (name "unconnected-(U103-BP-Pad4)") (class "Default")
      (node (ref "U103") (pin "4") (pinfunction "BP_4") (pintype "input"))
    )
  )
)
